# Sheet_1_2024-01-01_2.net
KiCad netlist of a schematic drawn in Altium Designer
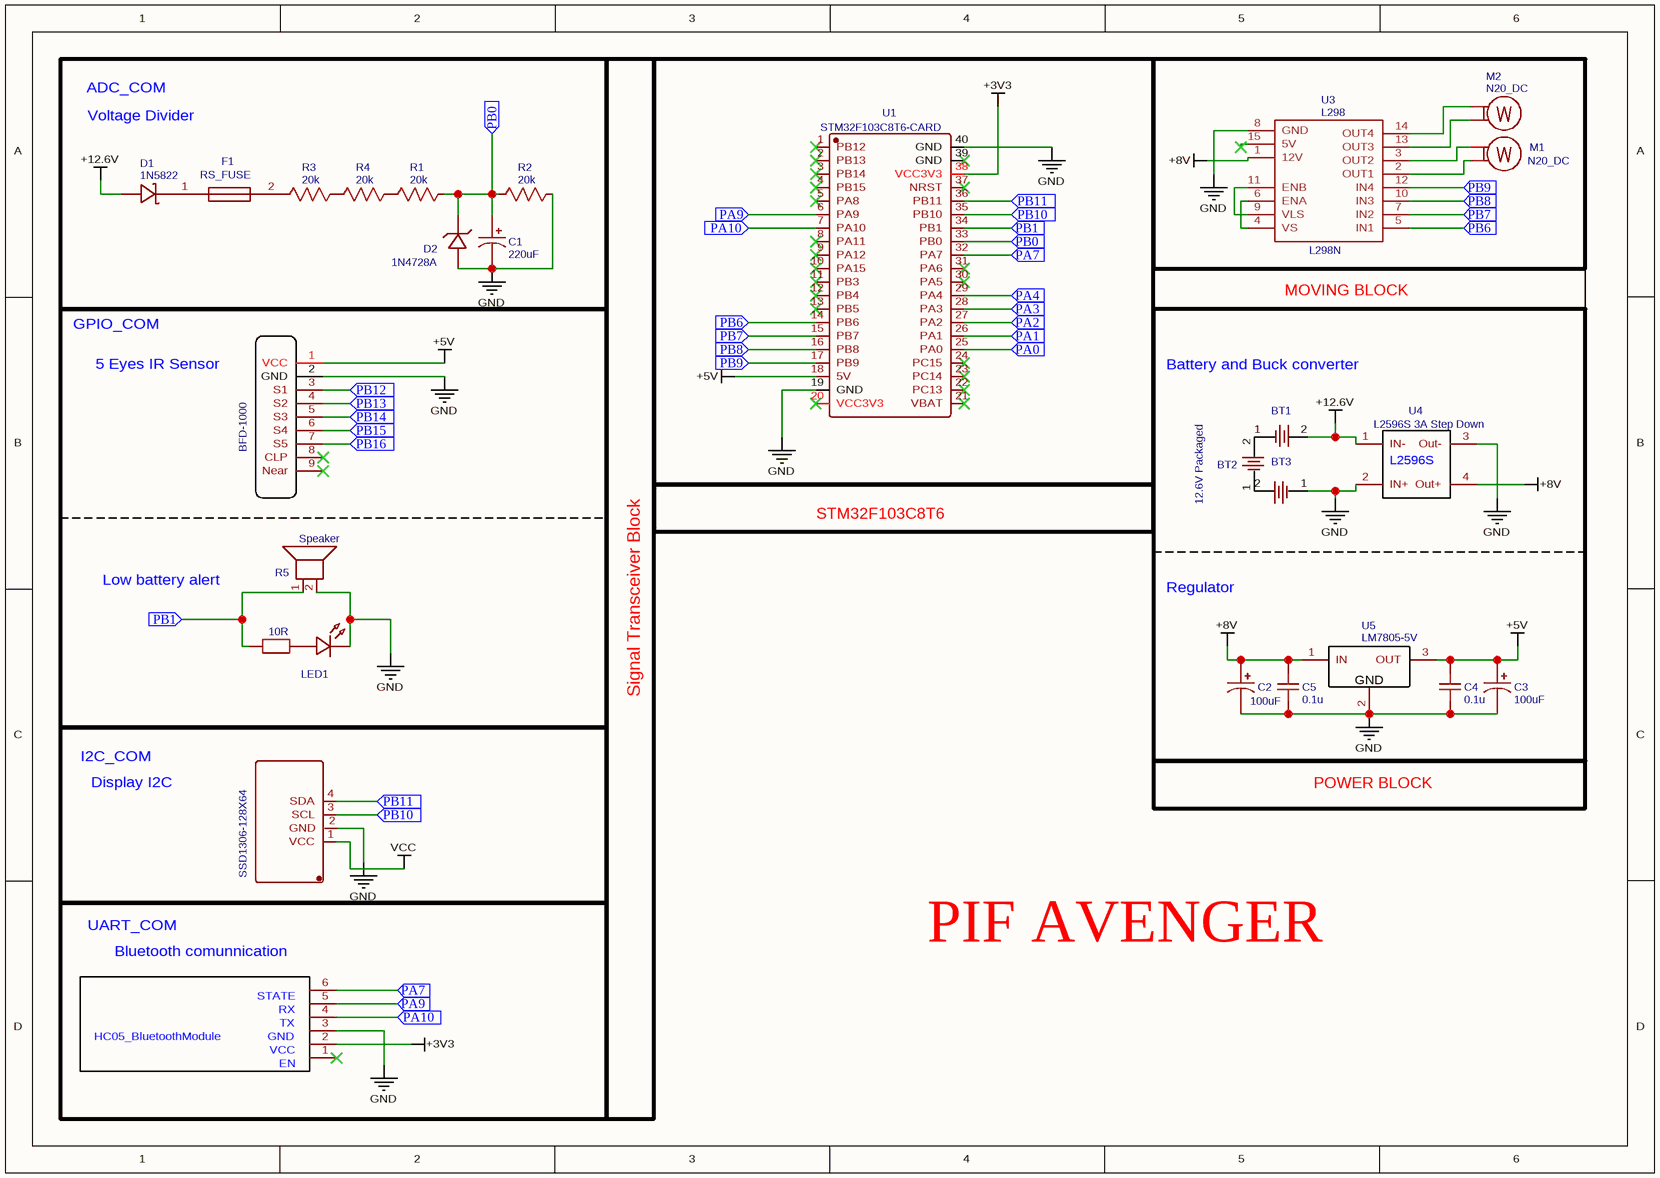
[diagram p0: Sheet_1_2024-01-01 (2).schdoc]

(export (version "E")
  (design (tool "Eeschema 10.0.6"))
  (components
    (comp (ref "BT1")
      (value "BH-18650-A1AJ006")
      (fields (field (name "MANUFACTURER") "MYOUNG(美阳)") (field (name "CONTRIBUTOR") "lcsc"))
      (libsource (lib "altium-import") (part "root_0_BH-18650-A1AJ006_"))
    )
    (comp (ref "BT2")
      (value "12.6V Packaged")
      (fields
        (field (name "MANUFACTURER") "MYOUNG(美阳)")
        (field (name "MANUFACTURER PART") "BH-18650-A1AJ006")
        (field (name "CONTRIBUTOR") "lcsc")
      )
      (libsource (lib "altium-import") (part "root_3_12.6V Packaged_"))
    )
    (comp (ref "BT3")
      (value "BH-18650-A1AJ006")
      (fields (field (name "MANUFACTURER") "MYOUNG(美阳)") (field (name "CONTRIBUTOR") "lcsc"))
      (libsource (lib "altium-import") (part "root_2_BH-18650-A1AJ006_"))
    )
    (comp (ref "C1")
      (value "220uF")
      (fields (field (name "CONTRIBUTOR") "LCEDA_Lib"))
      (libsource (lib "altium-import") (part "root_3_220uF_"))
    )
    (comp (ref "C2")
      (value "100uF")
      (fields (field (name "CONTRIBUTOR") "LCEDA_Lib"))
      (libsource (lib "altium-import") (part "root_3_100uF_"))
    )
    (comp (ref "C3")
      (value "100uF")
      (fields (field (name "CONTRIBUTOR") "LCEDA_Lib"))
      (libsource (lib "altium-import") (part "root_3_100uF_"))
    )
    (comp (ref "C4")
      (value "0.1u")
      (fields (field (name "CONTRIBUTOR") "LCEDA_Lib"))
      (libsource (lib "altium-import") (part "root_1_0.1u_"))
    )
    (comp (ref "C5")
      (value "0.1u")
      (fields (field (name "CONTRIBUTOR") "LCEDA_Lib"))
      (libsource (lib "altium-import") (part "root_1_0.1u_"))
    )
    (comp (ref "D1")
      (value "1N5822")
      (fields (field (name "MANUFACTURER") "MDD"))
      (libsource (lib "altium-import") (part "root_0_1N5822_"))
    )
    (comp (ref "D2")
      (value "1N4728A")
      (fields (field (name "MANUFACTURER") "onsemi(安森美)") (field (name "CONTRIBUTOR") "LCSC"))
      (libsource (lib "altium-import") (part "root_3_1N4728A_"))
    )
    (comp (ref "F1")
      (value "RS_FUSE")
      (fields (field (name "MANUFACTURER PART") "ResettableFuse-500mA") (field (name "CONTRIBUTOR") "LCSC"))
      (libsource (lib "altium-import") (part "root_0_RS_FUSE_"))
    )
    (comp (ref "LED1")
      (value "LED-0603_R")
      (fields
        (field (name "MANUFACTURER") "EVERLIGHT(台湾亿光)")
        (field (name "MANUFACTURER PART") "19-217/R6C-AL1M2VY/3T")
        (field (name "CONTRIBUTOR") "LCEDA_01")
      )
      (libsource (lib "altium-import") (part "root_0_LED-0603_R_"))
    )
    (comp (ref "LS1")
      (value "Speaker")
      (fields (field (name "CONTRIBUTOR") "virtualgt"))
      (libsource (lib "altium-import") (part "root_1_Speaker_"))
    )
    (comp (ref "M1")
      (value "N20_DC")
      (fields (field (name "CONTRIBUTOR") "crypt-pcb"))
      (libsource (lib "altium-import") (part "root_1_N20_DC_"))
    )
    (comp (ref "M2")
      (value "N20_DC")
      (fields (field (name "CONTRIBUTOR") "crypt-pcb"))
      (libsource (lib "altium-import") (part "root_1_N20_DC_"))
    )
    (comp (ref "PCB1")
      (value "SSD1306-128X64")
      (libsource (lib "altium-import") (part "root_2_SSD1306-128X64_"))
    )
    (comp (ref "R1")
      (value "20k")
      (fields (field (name "CONTRIBUTOR") "LCEDA_Lib"))
      (libsource (lib "altium-import") (part "root_0_20k_"))
    )
    (comp (ref "R2")
      (value "20k")
      (fields (field (name "CONTRIBUTOR") "LCEDA_Lib"))
      (libsource (lib "altium-import") (part "root_0_20k_"))
    )
    (comp (ref "R3")
      (value "20k")
      (fields (field (name "CONTRIBUTOR") "LCEDA_Lib"))
      (libsource (lib "altium-import") (part "root_0_20k_"))
    )
    (comp (ref "R4")
      (value "20k")
      (fields (field (name "CONTRIBUTOR") "LCEDA_Lib"))
      (libsource (lib "altium-import") (part "root_0_20k_"))
    )
    (comp (ref "R5")
      (value "10R")
      (fields (field (name "CONTRIBUTOR") "LCEDA_Lib"))
      (libsource (lib "altium-import") (part "root_0_10R_"))
    )
    (comp (ref "U1")
      (value "STM32F103C8T6-CARD")
      (fields (field (name "MANUFACTURER PART") "STM32F103C8T6-Card") (field (name "CONTRIBUTOR") "lcsc"))
      (libsource (lib "altium-import") (part "root_0_STM32F103C8T6-CARD_"))
    )
    (comp (ref "U2")
      (value "HC_05_Bluetooth")
      (fields (field (name "CONTRIBUTOR") "Crypt-PCB"))
      (libsource (lib "altium-import") (part "root_1_HC_05_Bluetooth_"))
    )
    (comp (ref "U3")
      (value "L298")
      (fields
        (field (name "MANUFACTURER PART") "L298N Driver")
        (field (name "CONTRIBUTOR") "huynhthienphu2492001")
      )
      (libsource (lib "altium-import") (part "root_2_L298_"))
    )
    (comp (ref "U4")
      (value "L2596S 3A Step Down")
      (fields (field (name "CONTRIBUTOR") "St1fT"))
      (libsource (lib "altium-import") (part "root_0_L2596S 3A Step Down_"))
    )
    (comp (ref "U5")
      (value "LM7805-5V")
      (fields (field (name "CONTRIBUTOR") "LCSC"))
      (libsource (lib "altium-import") (part "root_0_LM7805-5V_"))
    )
    (comp (ref "U6")
      (value "BFD-1000")
      (fields (field (name "CONTRIBUTOR") "mrpivato"))
      (libsource (lib "altium-import") (part "root_0_BFD-1000_"))
    )
  )
  (nets
    (net (code "1") (name "+3V3") (class "Default")
      (node (ref "U1") (pin "38") (pinfunction "VCC3V3_38") (pintype "passive"))
      (node (ref "U2") (pin "2") (pinfunction "2_2") (pintype "passive"))
    )
    (net (code "2") (name "+5V") (class "Default")
      (node (ref "C3") (pin "1") (pinfunction "1_1") (pintype "passive"))
      (node (ref "C4") (pin "2") (pinfunction "2_2") (pintype "passive"))
      (node (ref "U1") (pin "18") (pinfunction "5V_18") (pintype "passive"))
      (node (ref "U5") (pin "3") (pinfunction "OUT_3") (pintype "passive"))
      (node (ref "U6") (pin "1") (pinfunction "VCC_1") (pintype "passive"))
    )
    (net (code "3") (name "+8V") (class "Default")
      (node (ref "C2") (pin "1") (pinfunction "1_1") (pintype "passive"))
      (node (ref "C5") (pin "2") (pinfunction "2_2") (pintype "passive"))
      (node (ref "U3") (pin "1") (pinfunction "12V_1") (pintype "passive"))
      (node (ref "U4") (pin "4") (pinfunction "Out+_4") (pintype "passive"))
      (node (ref "U5") (pin "1") (pinfunction "IN_1") (pintype "passive"))
    )
    (net (code "4") (name "+12.6V") (class "Default")
      (node (ref "BT1") (pin "2") (pinfunction "2_2") (pintype "passive"))
      (node (ref "D1") (pin "1") (pinfunction "A_1") (pintype "passive"))
      (node (ref "U4") (pin "1") (pinfunction "IN-_1") (pintype "passive"))
    )
    (net (code "5") (name "/PA0") (class "Default")
      (node (ref "U1") (pin "25") (pinfunction "PA0_25") (pintype "passive"))
    )
    (net (code "6") (name "/PA1") (class "Default")
      (node (ref "U1") (pin "26") (pinfunction "PA1_26") (pintype "passive"))
    )
    (net (code "7") (name "/PA2") (class "Default")
      (node (ref "U1") (pin "27") (pinfunction "PA2_27") (pintype "passive"))
    )
    (net (code "8") (name "/PA3") (class "Default")
      (node (ref "U1") (pin "28") (pinfunction "PA3_28") (pintype "passive"))
    )
    (net (code "9") (name "/PA4") (class "Default")
      (node (ref "U1") (pin "29") (pinfunction "PA4_29") (pintype "passive"))
    )
    (net (code "10") (name "/PA7") (class "Default")
      (node (ref "U1") (pin "32") (pinfunction "PA7_32") (pintype "passive"))
      (node (ref "U2") (pin "6") (pinfunction "6_6") (pintype "passive"))
    )
    (net (code "11") (name "/PA9") (class "Default")
      (node (ref "U1") (pin "6") (pinfunction "PA9_6") (pintype "passive"))
      (node (ref "U2") (pin "5") (pinfunction "5_5") (pintype "passive"))
    )
    (net (code "12") (name "/PA10") (class "Default")
      (node (ref "U1") (pin "7") (pinfunction "PA10_7") (pintype "passive"))
      (node (ref "U2") (pin "4") (pinfunction "4_4") (pintype "passive"))
    )
    (net (code "13") (name "/PB0") (class "Default")
      (node (ref "C1") (pin "1") (pinfunction "1_1") (pintype "passive"))
      (node (ref "D2") (pin "1") (pinfunction "K_1") (pintype "passive"))
      (node (ref "R1") (pin "2") (pinfunction "2_2") (pintype "passive"))
      (node (ref "R2") (pin "1") (pinfunction "1_1") (pintype "passive"))
      (node (ref "U1") (pin "33") (pinfunction "PB0_33") (pintype "passive"))
    )
    (net (code "14") (name "/PB1") (class "Default")
      (node (ref "LS1") (pin "1") (pinfunction "1_1") (pintype "passive"))
      (node (ref "R5") (pin "1") (pinfunction "1_1") (pintype "passive"))
      (node (ref "U1") (pin "34") (pinfunction "PB1_34") (pintype "passive"))
    )
    (net (code "15") (name "/PB6") (class "Default")
      (node (ref "U1") (pin "14") (pinfunction "PB6_14") (pintype "passive"))
      (node (ref "U3") (pin "5") (pinfunction "IN1_5") (pintype "passive"))
    )
    (net (code "16") (name "/PB7") (class "Default")
      (node (ref "U1") (pin "15") (pinfunction "PB7_15") (pintype "passive"))
      (node (ref "U3") (pin "7") (pinfunction "IN2_7") (pintype "passive"))
    )
    (net (code "17") (name "/PB8") (class "Default")
      (node (ref "U1") (pin "16") (pinfunction "PB8_16") (pintype "passive"))
      (node (ref "U3") (pin "10") (pinfunction "IN3_10") (pintype "passive"))
    )
    (net (code "18") (name "/PB9") (class "Default")
      (node (ref "U1") (pin "17") (pinfunction "PB9_17") (pintype "passive"))
      (node (ref "U3") (pin "12") (pinfunction "IN4_12") (pintype "passive"))
    )
    (net (code "19") (name "/PB10") (class "Default")
      (node (ref "PCB1") (pin "3") (pinfunction "SCL_3") (pintype "passive"))
      (node (ref "U1") (pin "35") (pinfunction "PB10_35") (pintype "passive"))
    )
    (net (code "20") (name "/PB11") (class "Default")
      (node (ref "PCB1") (pin "4") (pinfunction "SDA_4") (pintype "passive"))
      (node (ref "U1") (pin "36") (pinfunction "PB11_36") (pintype "passive"))
    )
    (net (code "21") (name "/PB12") (class "Default")
      (node (ref "U6") (pin "3") (pinfunction "S1_3") (pintype "passive"))
    )
    (net (code "22") (name "/PB13") (class "Default")
      (node (ref "U6") (pin "4") (pinfunction "S2_4") (pintype "passive"))
    )
    (net (code "23") (name "/PB14") (class "Default")
      (node (ref "U6") (pin "5") (pinfunction "S3_5") (pintype "passive"))
    )
    (net (code "24") (name "/PB15") (class "Default")
      (node (ref "U6") (pin "6") (pinfunction "S4_6") (pintype "passive"))
    )
    (net (code "25") (name "/PB16") (class "Default")
      (node (ref "U6") (pin "7") (pinfunction "S5_7") (pintype "passive"))
    )
    (net (code "26") (name "GND") (class "Default")
      (node (ref "BT3") (pin "1") (pinfunction "1_1") (pintype "passive"))
      (node (ref "C1") (pin "2") (pinfunction "2_2") (pintype "passive"))
      (node (ref "C2") (pin "2") (pinfunction "2_2") (pintype "passive"))
      (node (ref "C3") (pin "2") (pinfunction "2_2") (pintype "passive"))
      (node (ref "C4") (pin "1") (pinfunction "1_1") (pintype "passive"))
      (node (ref "C5") (pin "1") (pinfunction "1_1") (pintype "passive"))
      (node (ref "D2") (pin "2") (pinfunction "A_2") (pintype "passive"))
      (node (ref "LED1") (pin "2") (pinfunction "2_2") (pintype "passive"))
      (node (ref "LS1") (pin "2") (pinfunction "2_2") (pintype "passive"))
      (node (ref "PCB1") (pin "2") (pinfunction "GND_2") (pintype "passive"))
      (node (ref "R2") (pin "2") (pinfunction "2_2") (pintype "passive"))
      (node (ref "U1") (pin "19") (pinfunction "GND_19") (pintype "passive"))
      (node (ref "U1") (pin "40") (pinfunction "GND_40") (pintype "passive"))
      (node (ref "U2") (pin "3") (pinfunction "3_3") (pintype "passive"))
      (node (ref "U3") (pin "8") (pinfunction "GND_8") (pintype "passive"))
      (node (ref "U4") (pin "2") (pinfunction "IN+_2") (pintype "passive"))
      (node (ref "U4") (pin "3") (pinfunction "Out-_3") (pintype "passive"))
      (node (ref "U5") (pin "2") (pinfunction "GND_2") (pintype "passive"))
      (node (ref "U6") (pin "2") (pinfunction "GND_2") (pintype "passive"))
    )
    (net (code "27") (name "Net-(BT1-Pad1)") (class "Default")
      (node (ref "BT1") (pin "1") (pinfunction "1_1") (pintype "passive"))
      (node (ref "BT2") (pin "2") (pinfunction "2_2") (pintype "passive"))
    )
    (net (code "28") (name "Net-(BT2-Pad1)") (class "Default")
      (node (ref "BT2") (pin "1") (pinfunction "1_1") (pintype "passive"))
      (node (ref "BT3") (pin "2") (pinfunction "2_2") (pintype "passive"))
    )
    (net (code "29") (name "Net-(D1-K)") (class "Default")
      (node (ref "D1") (pin "2") (pinfunction "K_2") (pintype "passive"))
      (node (ref "F1") (pin "1") (pinfunction "1_1") (pintype "passive"))
    )
    (net (code "30") (name "Net-(F1-Pad2)") (class "Default")
      (node (ref "F1") (pin "2") (pinfunction "2_2") (pintype "passive"))
      (node (ref "R3") (pin "1") (pinfunction "1_1") (pintype "passive"))
    )
    (net (code "31") (name "Net-(M1-+)") (class "Default")
      (node (ref "M1") (pin "2") (pinfunction "+_2") (pintype "passive"))
      (node (ref "U3") (pin "2") (pinfunction "OUT1_2") (pintype "passive"))
    )
    (net (code "32") (name "Net-(M1--)") (class "Default")
      (node (ref "M1") (pin "1") (pinfunction "-_1") (pintype "passive"))
      (node (ref "U3") (pin "3") (pinfunction "OUT2_3") (pintype "passive"))
    )
    (net (code "33") (name "Net-(M2-+)") (class "Default")
      (node (ref "M2") (pin "2") (pinfunction "+_2") (pintype "passive"))
      (node (ref "U3") (pin "13") (pinfunction "OUT3_13") (pintype "passive"))
    )
    (net (code "34") (name "Net-(M2--)") (class "Default")
      (node (ref "M2") (pin "1") (pinfunction "-_1") (pintype "passive"))
      (node (ref "U3") (pin "14") (pinfunction "OUT4_14") (pintype "passive"))
    )
    (net (code "35") (name "Net-(R1-Pad1)") (class "Default")
      (node (ref "R1") (pin "1") (pinfunction "1_1") (pintype "passive"))
      (node (ref "R4") (pin "2") (pinfunction "2_2") (pintype "passive"))
    )
    (net (code "36") (name "Net-(R3-Pad2)") (class "Default")
      (node (ref "R3") (pin "2") (pinfunction "2_2") (pintype "passive"))
      (node (ref "R4") (pin "1") (pinfunction "1_1") (pintype "passive"))
    )
    (net (code "37") (name "Net-(U3-ENA)") (class "Default")
      (node (ref "U3") (pin "4") (pinfunction "VS_4") (pintype "passive"))
      (node (ref "U3") (pin "6") (pinfunction "ENA_6") (pintype "passive"))
    )
    (net (code "38") (name "Net-(U3-ENB)") (class "Default")
      (node (ref "U3") (pin "11") (pinfunction "ENB_11") (pintype "passive"))
      (node (ref "U3") (pin "9") (pinfunction "VLS_9") (pintype "passive"))
    )
    (net (code "39") (name "VCC") (class "Default")
      (node (ref "PCB1") (pin "1") (pinfunction "VCC_1") (pintype "passive"))
    )
    (net (code "40") (name "unconnected-(LED1-Pad1)") (class "Default")
      (node (ref "LED1") (pin "1") (pinfunction "1_1") (pintype "passive"))
    )
    (net (code "41") (name "unconnected-(R5-Pad2)") (class "Default")
      (node (ref "R5") (pin "2") (pinfunction "2_2") (pintype "passive"))
    )
    (net (code "42") (name "unconnected-(U1-GND-Pad39)") (class "Default")
      (node (ref "U1") (pin "39") (pinfunction "GND_39") (pintype "passive+no_connect"))
    )
    (net (code "43") (name "unconnected-(U1-NRST-Pad37)") (class "Default")
      (node (ref "U1") (pin "37") (pinfunction "NRST_37") (pintype "passive+no_connect"))
    )
    (net (code "44") (name "unconnected-(U1-PA5-Pad30)") (class "Default")
      (node (ref "U1") (pin "30") (pinfunction "PA5_30") (pintype "passive+no_connect"))
    )
    (net (code "45") (name "unconnected-(U1-PA6-Pad31)") (class "Default")
      (node (ref "U1") (pin "31") (pinfunction "PA6_31") (pintype "passive+no_connect"))
    )
    (net (code "46") (name "unconnected-(U1-PA8-Pad5)") (class "Default")
      (node (ref "U1") (pin "5") (pinfunction "PA8_5") (pintype "passive+no_connect"))
    )
    (net (code "47") (name "unconnected-(U1-PA11-Pad8)") (class "Default")
      (node (ref "U1") (pin "8") (pinfunction "PA11_8") (pintype "passive+no_connect"))
    )
    (net (code "48") (name "unconnected-(U1-PA12-Pad9)") (class "Default")
      (node (ref "U1") (pin "9") (pinfunction "PA12_9") (pintype "passive+no_connect"))
    )
    (net (code "49") (name "unconnected-(U1-PA15-Pad10)") (class "Default")
      (node (ref "U1") (pin "10") (pinfunction "PA15_10") (pintype "passive+no_connect"))
    )
    (net (code "50") (name "unconnected-(U1-PB3-Pad11)") (class "Default")
      (node (ref "U1") (pin "11") (pinfunction "PB3_11") (pintype "passive+no_connect"))
    )
    (net (code "51") (name "unconnected-(U1-PB4-Pad12)") (class "Default")
      (node (ref "U1") (pin "12") (pinfunction "PB4_12") (pintype "passive+no_connect"))
    )
    (net (code "52") (name "unconnected-(U1-PB5-Pad13)") (class "Default")
      (node (ref "U1") (pin "13") (pinfunction "PB5_13") (pintype "passive+no_connect"))
    )
    (net (code "53") (name "unconnected-(U1-PB12-Pad1)") (class "Default")
      (node (ref "U1") (pin "1") (pinfunction "PB12_1") (pintype "passive+no_connect"))
    )
    (net (code "54") (name "unconnected-(U1-PB13-Pad2)") (class "Default")
      (node (ref "U1") (pin "2") (pinfunction "PB13_2") (pintype "passive+no_connect"))
    )
    (net (code "55") (name "unconnected-(U1-PB14-Pad3)") (class "Default")
      (node (ref "U1") (pin "3") (pinfunction "PB14_3") (pintype "passive+no_connect"))
    )
    (net (code "56") (name "unconnected-(U1-PB15-Pad4)") (class "Default")
      (node (ref "U1") (pin "4") (pinfunction "PB15_4") (pintype "passive+no_connect"))
    )
    (net (code "57") (name "unconnected-(U1-PC13-Pad22)") (class "Default")
      (node (ref "U1") (pin "22") (pinfunction "PC13_22") (pintype "passive+no_connect"))
    )
    (net (code "58") (name "unconnected-(U1-PC14-Pad23)") (class "Default")
      (node (ref "U1") (pin "23") (pinfunction "PC14_23") (pintype "passive+no_connect"))
    )
    (net (code "59") (name "unconnected-(U1-PC15-Pad24)") (class "Default")
      (node (ref "U1") (pin "24") (pinfunction "PC15_24") (pintype "passive+no_connect"))
    )
    (net (code "60") (name "unconnected-(U1-VBAT-Pad21)") (class "Default")
      (node (ref "U1") (pin "21") (pinfunction "VBAT_21") (pintype "passive+no_connect"))
    )
    (net (code "61") (name "unconnected-(U1-VCC3V3-Pad20)") (class "Default")
      (node (ref "U1") (pin "20") (pinfunction "VCC3V3_20") (pintype "passive+no_connect"))
    )
    (net (code "62") (name "unconnected-(U2-Pad1)") (class "Default")
      (node (ref "U2") (pin "1") (pinfunction "1_1") (pintype "passive+no_connect"))
    )
    (net (code "63") (name "unconnected-(U3-5V-Pad15)") (class "Default")
      (node (ref "U3") (pin "15") (pinfunction "5V_15") (pintype "passive+no_connect"))
    )
    (net (code "64") (name "unconnected-(U6-CLP-Pad8)") (class "Default")
      (node (ref "U6") (pin "8") (pinfunction "CLP_8") (pintype "passive+no_connect"))
    )
    (net (code "65") (name "unconnected-(U6-Near-Pad9)") (class "Default")
      (node (ref "U6") (pin "9") (pinfunction "Near_9") (pintype "passive+no_connect"))
    )
  )
)
